# zeta2rework_lw_v28_rework.net
KiCad netlist of a schematic drawn in EAGLE
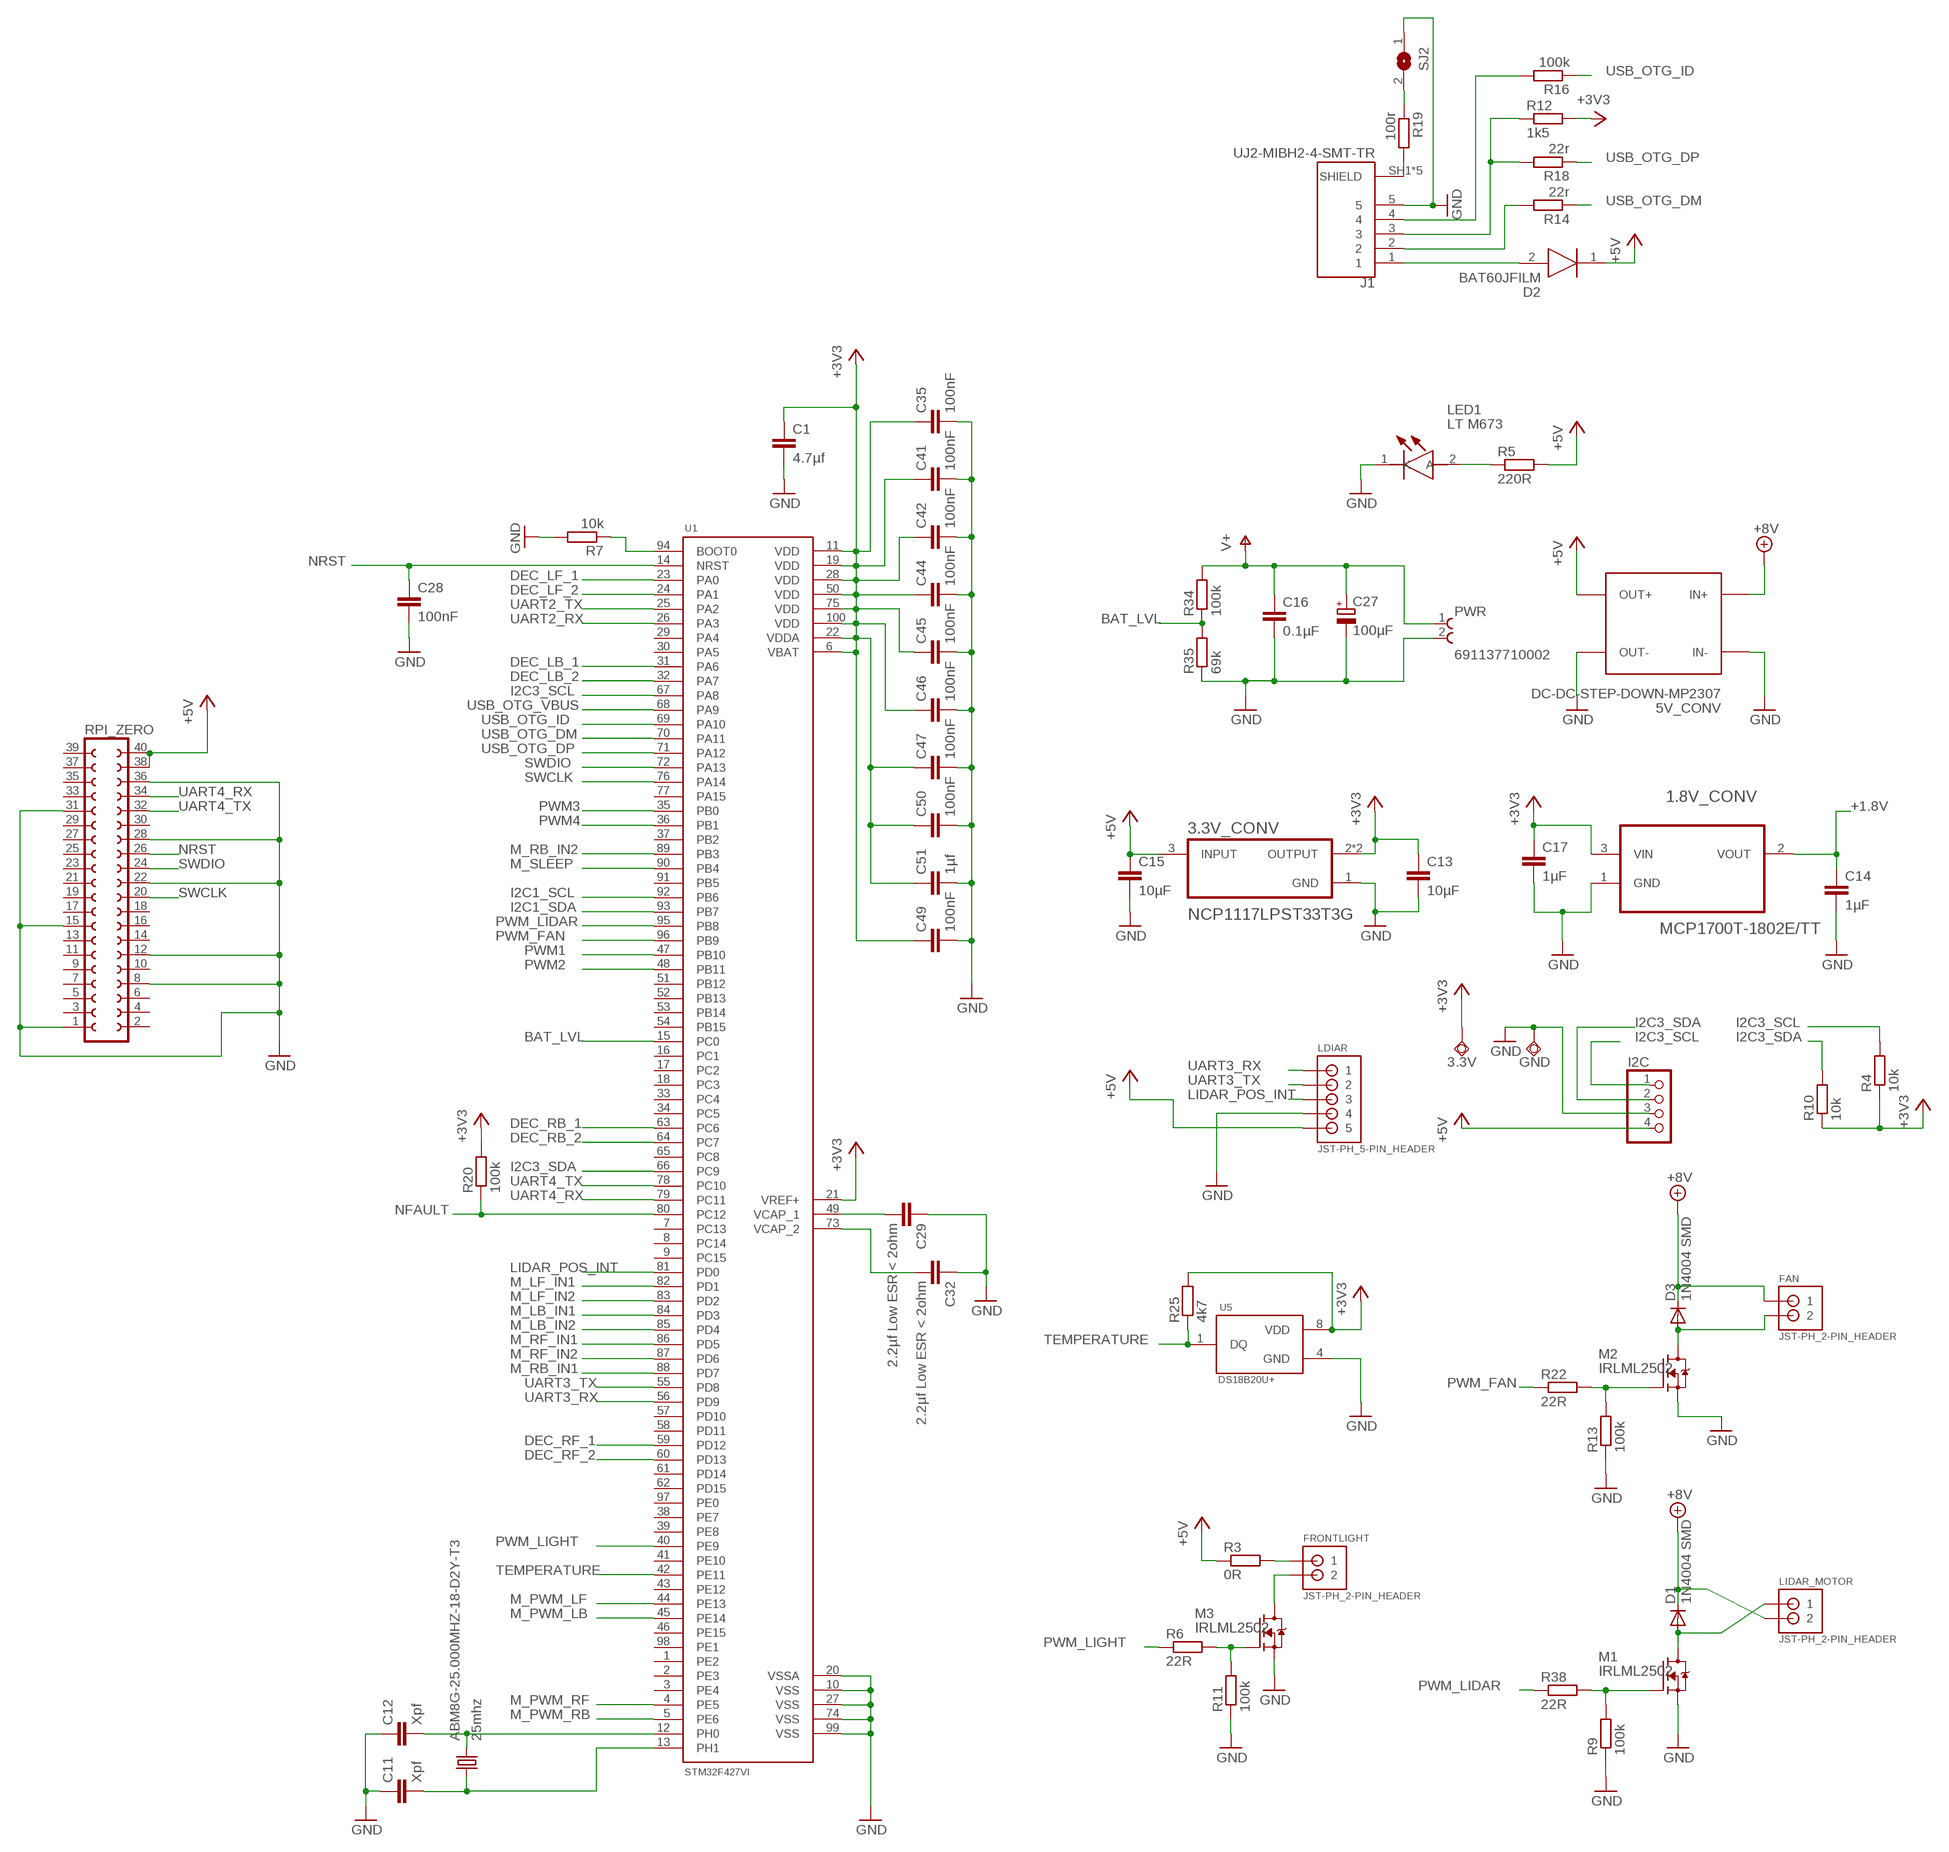
[diagram p0: schematic, sheet 1, part 1 of 2]
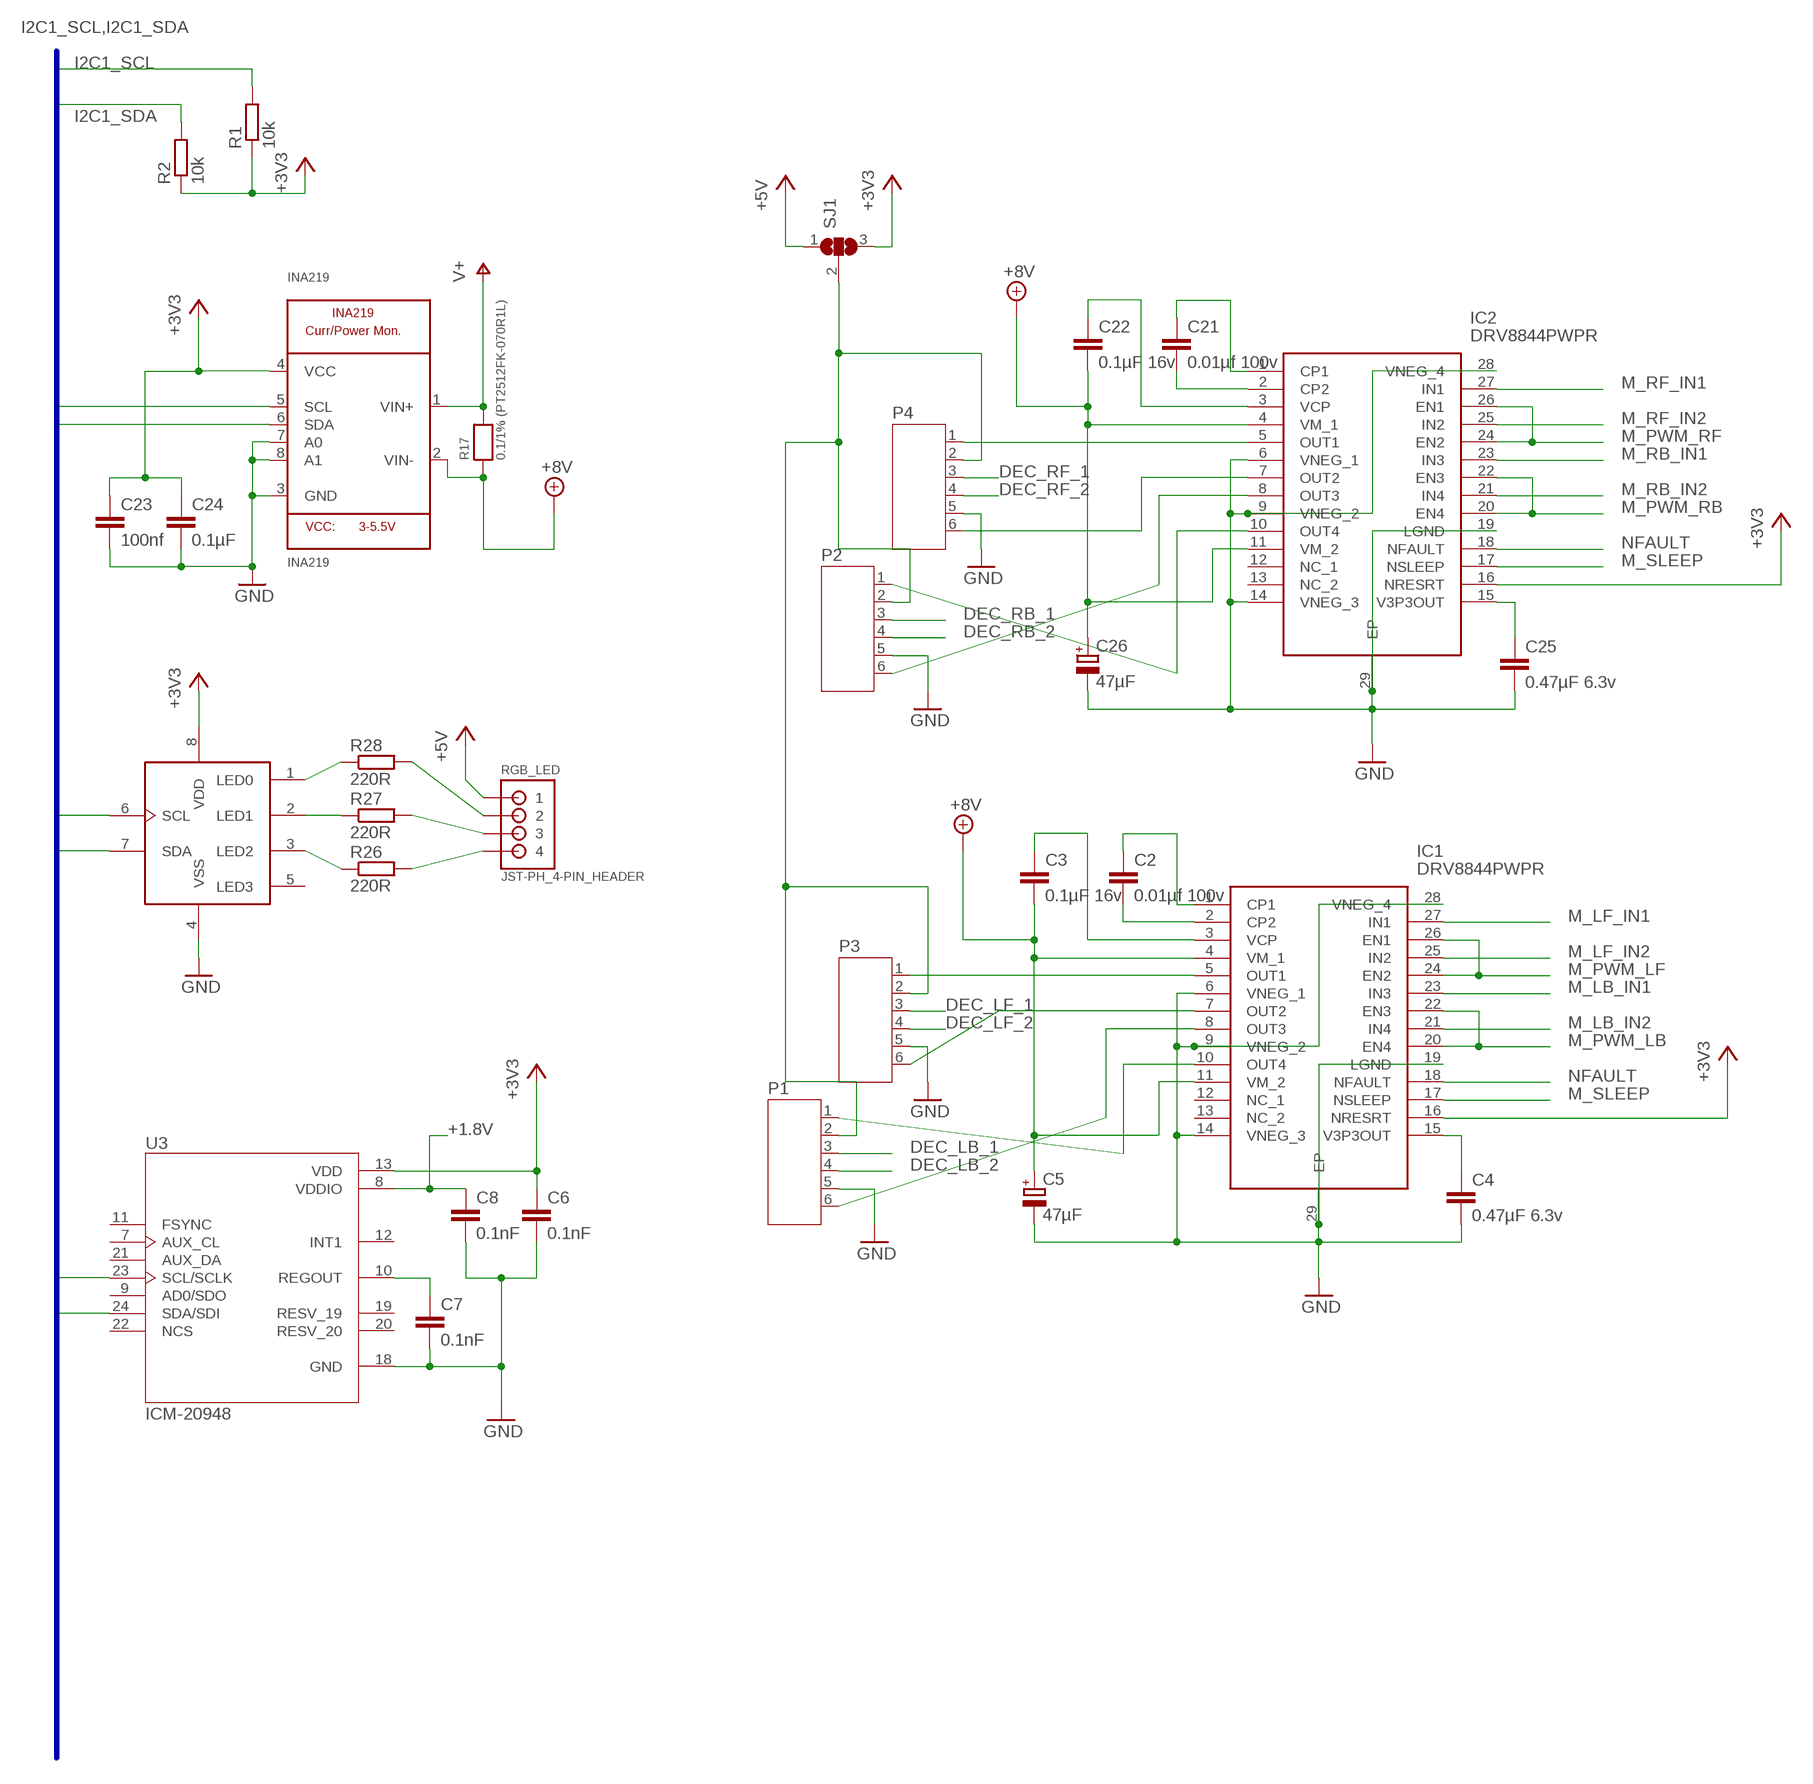
[diagram p1: schematic, sheet 1, part 2 of 2]

(export (version "E")
  (design (tool "Eeschema 10.0.6"))
  (components
    (comp (ref "1.8V_CONV")
      (value "MCP1700T-1802E/TT")
      (footprint "eagle-import:SOT95P237X112-3N")
      (fields (field (name "MF") "Microchip") (field (name "MP") "MCP1700T-2102E/TT"))
      (libsource (lib "eagle-import") (part "MCP1700T-2102E/TT"))
    )
    (comp (ref "3.3V")
      (value "TPSQTP20R")
      (footprint "eagle-import:TP20R")
      (libsource (lib "eagle-import") (part "TPSQTP20R"))
    )
    (comp (ref "3.3V_CONV")
      (value "NCP1117LPST33T3G")
      (footprint "eagle-import:SOT230P700X175-4N")
      (fields (field (name "MF") "ON Semiconductor"))
      (libsource (lib "eagle-import") (part "NCP1117LPST33T3G"))
    )
    (comp (ref "5V_CONV")
      (value "DC-DC-STEP-DOWN-MP2307")
      (footprint "eagle-import:DC-DC-STEP-DOWN-MP2307")
      (libsource (lib "eagle-import") (part "DC-DC-STEP-DOWN-MP2307"))
    )
    (comp (ref "ABM8G-25.000MHZ-18-D2Y-T3")
      (value "25mhz")
      (footprint "eagle-import:5.0X3.2_KX-9A")
      (libsource (lib "eagle-import") (part "KX-9A"))
    )
    (comp (ref "C1")
      (value "4.7µf")
      (footprint "eagle-import:C0603")
      (libsource (lib "eagle-import") (part "C-EUC0603"))
    )
    (comp (ref "C2")
      (value "0.01µf 100v")
      (footprint "eagle-import:C0603")
      (libsource (lib "eagle-import") (part "C-EUC0603"))
    )
    (comp (ref "C3")
      (value "0.1µF 16v")
      (footprint "eagle-import:C0603")
      (libsource (lib "eagle-import") (part "C-EUC0603"))
    )
    (comp (ref "C4")
      (value "0.47µF 6.3v")
      (footprint "eagle-import:C0603")
      (libsource (lib "eagle-import") (part "C-EUC0603"))
    )
    (comp (ref "C5")
      (value "47µF")
      (footprint "eagle-import:UD-5X5,8_NICHICON")
      (libsource (lib "eagle-import") (part "CPOL-EUUD-5X5,8"))
    )
    (comp (ref "C6")
      (value "0.1nF")
      (footprint "eagle-import:C0603")
      (libsource (lib "eagle-import") (part "C-EUC0603"))
    )
    (comp (ref "C7")
      (value "0.1nF")
      (footprint "eagle-import:C0603")
      (libsource (lib "eagle-import") (part "C-EUC0603"))
    )
    (comp (ref "C8")
      (value "0.1nF")
      (footprint "eagle-import:C0603")
      (libsource (lib "eagle-import") (part "C-EUC0603"))
    )
    (comp (ref "C11")
      (value "Xpf")
      (footprint "eagle-import:C0603")
      (libsource (lib "eagle-import") (part "C-EUC0603"))
    )
    (comp (ref "C12")
      (value "Xpf")
      (footprint "eagle-import:C0603")
      (libsource (lib "eagle-import") (part "C-EUC0603"))
    )
    (comp (ref "C13")
      (value "10µF")
      (footprint "eagle-import:C1206")
      (libsource (lib "eagle-import") (part "C-EUC1206"))
    )
    (comp (ref "C14")
      (value "1µF")
      (footprint "eagle-import:C0603")
      (libsource (lib "eagle-import") (part "C-EUC0603"))
    )
    (comp (ref "C15")
      (value "10µF")
      (footprint "eagle-import:C1206")
      (libsource (lib "eagle-import") (part "C-EUC1206"))
    )
    (comp (ref "C16")
      (value "0.1µF")
      (footprint "eagle-import:C0603")
      (libsource (lib "eagle-import") (part "C-EUC0603"))
    )
    (comp (ref "C17")
      (value "1µF")
      (footprint "eagle-import:C0603")
      (libsource (lib "eagle-import") (part "C-EUC0603"))
    )
    (comp (ref "C21")
      (value "0.01µf 100v")
      (footprint "eagle-import:C0603")
      (libsource (lib "eagle-import") (part "C-EUC0603"))
    )
    (comp (ref "C22")
      (value "0.1µF 16v")
      (footprint "eagle-import:C0603")
      (libsource (lib "eagle-import") (part "C-EUC0603"))
    )
    (comp (ref "C23")
      (value "100nf")
      (footprint "eagle-import:C0603")
      (libsource (lib "eagle-import") (part "C-EUC0603"))
    )
    (comp (ref "C24")
      (value "0.1µF")
      (footprint "eagle-import:C0603")
      (libsource (lib "eagle-import") (part "C-EUC0603"))
    )
    (comp (ref "C25")
      (value "0.47µF 6.3v")
      (footprint "eagle-import:C0603")
      (libsource (lib "eagle-import") (part "C-EUC0603"))
    )
    (comp (ref "C26")
      (value "47µF")
      (footprint "eagle-import:UD-5X5,8_NICHICON")
      (libsource (lib "eagle-import") (part "CPOL-EUUD-5X5,8"))
    )
    (comp (ref "C27")
      (value "100µF")
      (footprint "eagle-import:UD-5X5,8_NICHICON")
      (libsource (lib "eagle-import") (part "CPOL-EUUD-5X5,8"))
    )
    (comp (ref "C28")
      (value "100nF")
      (footprint "eagle-import:C0603")
      (libsource (lib "eagle-import") (part "C-EUC0603"))
    )
    (comp (ref "C29")
      (value "2.2µf Low ESR < 2ohm")
      (footprint "eagle-import:C1206")
      (libsource (lib "eagle-import") (part "C-EUC1206"))
    )
    (comp (ref "C32")
      (value "2.2µf Low ESR < 2ohm")
      (footprint "eagle-import:C1206")
      (libsource (lib "eagle-import") (part "C-EUC1206"))
    )
    (comp (ref "C35")
      (value "100nF")
      (footprint "eagle-import:C0603")
      (libsource (lib "eagle-import") (part "C-EUC0603"))
    )
    (comp (ref "C41")
      (value "100nF")
      (footprint "eagle-import:C0603")
      (libsource (lib "eagle-import") (part "C-EUC0603"))
    )
    (comp (ref "C42")
      (value "100nF")
      (footprint "eagle-import:C0603")
      (libsource (lib "eagle-import") (part "C-EUC0603"))
    )
    (comp (ref "C44")
      (value "100nF")
      (footprint "eagle-import:C0603")
      (libsource (lib "eagle-import") (part "C-EUC0603"))
    )
    (comp (ref "C45")
      (value "100nF")
      (footprint "eagle-import:C0603")
      (libsource (lib "eagle-import") (part "C-EUC0603"))
    )
    (comp (ref "C46")
      (value "100nF")
      (footprint "eagle-import:C0603")
      (libsource (lib "eagle-import") (part "C-EUC0603"))
    )
    (comp (ref "C47")
      (value "100nF")
      (footprint "eagle-import:C0603")
      (libsource (lib "eagle-import") (part "C-EUC0603"))
    )
    (comp (ref "C49")
      (value "100nF")
      (footprint "eagle-import:C0603")
      (libsource (lib "eagle-import") (part "C-EUC0603"))
    )
    (comp (ref "C50")
      (value "100nF")
      (footprint "eagle-import:C0603")
      (libsource (lib "eagle-import") (part "C-EUC0603"))
    )
    (comp (ref "C51")
      (value "1µf")
      (footprint "eagle-import:C0603")
      (libsource (lib "eagle-import") (part "C-EUC0603"))
    )
    (comp (ref "D1")
      (value "1N4004 SMD")
      (footprint "eagle-import:DO214AC")
      (libsource (lib "eagle-import") (part "DIODE-DO214AC"))
    )
    (comp (ref "D2")
      (value "BAT60JFILM")
      (footprint "eagle-import:SOD2513X117N")
      (fields (field (name "MOUSER_PART_NUMBER") "511-BAT60JFILM") (field (name "RS_PART_NUMBER") "1458781"))
      (libsource (lib "eagle-import") (part "BAT60JFILM"))
    )
    (comp (ref "D3")
      (value "1N4004 SMD")
      (footprint "eagle-import:DO214AC")
      (libsource (lib "eagle-import") (part "DIODE-DO214AC"))
    )
    (comp (ref "FAN")
      (value "JST-PH_2-PIN_HEADER")
      (footprint "eagle-import:JST_B2B-PH_HEADER")
      (libsource (lib "eagle-import") (part "JST-PH_2-PIN_HEADER"))
    )
    (comp (ref "FRONTLIGHT")
      (value "JST-PH_2-PIN_HEADER")
      (footprint "eagle-import:JST_B2B-PH_HEADER")
      (libsource (lib "eagle-import") (part "JST-PH_2-PIN_HEADER"))
    )
    (comp (ref "GND")
      (value "TPSQTP20R")
      (footprint "eagle-import:TP20R")
      (libsource (lib "eagle-import") (part "TPSQTP20R"))
    )
    (comp (ref "I2C")
      (value "PINHD-1X4")
      (footprint "eagle-import:1X04")
      (libsource (lib "eagle-import") (part "PINHD-1X4"))
    )
    (comp (ref "IC1")
      (value "DRV8844PWPR")
      (footprint "eagle-import:SOP65P640X120-29N")
      (fields (field (name "MOUSER_PART_NUMBER") "595-DRV8844PWPR"))
      (libsource (lib "eagle-import") (part "DRV8844PWPR"))
    )
    (comp (ref "IC2")
      (value "DRV8844PWPR")
      (footprint "eagle-import:SOP65P640X120-29N")
      (fields (field (name "MOUSER_PART_NUMBER") "595-DRV8844PWPR"))
      (libsource (lib "eagle-import") (part "DRV8844PWPR"))
    )
    (comp (ref "INA219")
      (value "INA219")
      (footprint "eagle-import:SOT23-8")
      (fields (field (name "MF") "Texas Instruments"))
      (libsource (lib "eagle-import") (part "INA219"))
    )
    (comp (ref "J1")
      (value "UJ2-MIBH2-4-SMT-TR")
      (footprint "eagle-import:CUI_UJ2-MIBH2-4-SMT-TR")
      (fields (field (name "MF") "CUI Inc."))
      (libsource (lib "eagle-import") (part "UJ2-MIBH2-4-SMT-TR"))
    )
    (comp (ref "LDIAR")
      (value "JST-PH_5-PIN_HEADER")
      (footprint "eagle-import:JST_B5B-PH_HEADER")
      (libsource (lib "eagle-import") (part "JST-PH_5-PIN_HEADER"))
    )
    (comp (ref "LED1")
      (value "LT M673")
      (footprint "eagle-import:LTM673-N1R2-25")
      (fields
        (field (name "MANUFACTURER_PART_NUMBER") "LT M673-N1R2-25")
        (field (name "MOUSER_PART_NUMBER") "720-LTM673N1R225Z")
        (field (name "RS_PART_NUMBER") "9133231")
      )
      (libsource (lib "eagle-import") (part "LT_M673-N1R2-25"))
    )
    (comp (ref "LIDAR_MOTOR")
      (value "JST-PH_2-PIN_HEADER")
      (footprint "eagle-import:JST_B2B-PH_HEADER")
      (libsource (lib "eagle-import") (part "JST-PH_2-PIN_HEADER"))
    )
    (comp (ref "M1")
      (value "IRLML2502")
      (footprint "eagle-import:SOT23")
      (fields (field (name "MF") "Infineon") (field (name "MP") "IRLML2502TRPBF"))
      (libsource (lib "eagle-import") (part "IRLML2502TRPBF"))
    )
    (comp (ref "M2")
      (value "IRLML2502")
      (footprint "eagle-import:SOT23")
      (fields (field (name "MF") "Infineon") (field (name "MP") "IRLML2502TRPBF"))
      (libsource (lib "eagle-import") (part "IRLML2502TRPBF"))
    )
    (comp (ref "M3")
      (value "IRLML2502")
      (footprint "eagle-import:SOT23")
      (fields (field (name "MF") "Infineon") (field (name "MP") "IRLML2502TRPBF"))
      (libsource (lib "eagle-import") (part "IRLML2502TRPBF"))
    )
    (comp (ref "P1")
      (value "JST-PH6")
      (footprint "eagle-import:JST-PH6")
      (libsource (lib "eagle-import") (part "JST-PH6"))
    )
    (comp (ref "P2")
      (value "JST-PH6")
      (footprint "eagle-import:JST-PH6")
      (libsource (lib "eagle-import") (part "JST-PH6"))
    )
    (comp (ref "P3")
      (value "JST-PH6")
      (footprint "eagle-import:JST-PH6")
      (libsource (lib "eagle-import") (part "JST-PH6"))
    )
    (comp (ref "P4")
      (value "JST-PH6")
      (footprint "eagle-import:JST-PH6")
      (libsource (lib "eagle-import") (part "JST-PH6"))
    )
    (comp (ref "PCA9533")
      (value "PCA9533")
      (footprint "eagle-import:SOIC8")
      (libsource (lib "eagle-import") (part "PCA9533"))
    )
    (comp (ref "PWR")
      (value "691137710002")
      (footprint "eagle-import:691137710002")
      (fields (field (name "MF") "Wurth Electronics"))
      (libsource (lib "eagle-import") (part "691137710002"))
    )
    (comp (ref "R1")
      (value "10k")
      (footprint "eagle-import:R0603")
      (libsource (lib "eagle-import") (part "R-EU_R0603"))
    )
    (comp (ref "R2")
      (value "10k")
      (footprint "eagle-import:R0603")
      (libsource (lib "eagle-import") (part "R-EU_R0603"))
    )
    (comp (ref "R3")
      (value "0R")
      (footprint "eagle-import:R0603")
      (libsource (lib "eagle-import") (part "R-EU_R0603"))
    )
    (comp (ref "R4")
      (value "10k")
      (footprint "eagle-import:R0603")
      (libsource (lib "eagle-import") (part "R-EU_R0603"))
    )
    (comp (ref "R5")
      (value "220R")
      (footprint "eagle-import:R0603")
      (libsource (lib "eagle-import") (part "R-EU_R0603"))
    )
    (comp (ref "R6")
      (value "22R")
      (footprint "eagle-import:R0603")
      (libsource (lib "eagle-import") (part "R-EU_R0603"))
    )
    (comp (ref "R7")
      (value "10k")
      (footprint "eagle-import:R0603")
      (libsource (lib "eagle-import") (part "R-EU_R0603"))
    )
    (comp (ref "R9")
      (value "100k")
      (footprint "eagle-import:R0603")
      (libsource (lib "eagle-import") (part "R-EU_R0603"))
    )
    (comp (ref "R10")
      (value "10k")
      (footprint "eagle-import:R0603")
      (libsource (lib "eagle-import") (part "R-EU_R0603"))
    )
    (comp (ref "R11")
      (value "100k")
      (footprint "eagle-import:R0603")
      (libsource (lib "eagle-import") (part "R-EU_R0603"))
    )
    (comp (ref "R12")
      (value "1k5")
      (footprint "eagle-import:R0603")
      (libsource (lib "eagle-import") (part "R-EU_R0603"))
    )
    (comp (ref "R13")
      (value "100k")
      (footprint "eagle-import:R0603")
      (libsource (lib "eagle-import") (part "R-EU_R0603"))
    )
    (comp (ref "R14")
      (value "22r")
      (footprint "eagle-import:R0603")
      (libsource (lib "eagle-import") (part "R-EU_R0603"))
    )
    (comp (ref "R16")
      (value "100k")
      (footprint "eagle-import:R0603")
      (libsource (lib "eagle-import") (part "R-EU_R0603"))
    )
    (comp (ref "R17")
      (value "0.1/1% (PT2512FK-070R1L)")
      (footprint "eagle-import:2512")
      (libsource (lib "eagle-import") (part "RESISTOR2512"))
    )
    (comp (ref "R18")
      (value "22r")
      (footprint "eagle-import:R0603")
      (libsource (lib "eagle-import") (part "R-EU_R0603"))
    )
    (comp (ref "R19")
      (value "100r")
      (footprint "eagle-import:R0603")
      (libsource (lib "eagle-import") (part "R-EU_R0603"))
    )
    (comp (ref "R20")
      (value "100k")
      (footprint "eagle-import:R0603")
      (libsource (lib "eagle-import") (part "R-EU_R0603"))
    )
    (comp (ref "R22")
      (value "22R")
      (footprint "eagle-import:R0603")
      (libsource (lib "eagle-import") (part "R-EU_R0603"))
    )
    (comp (ref "R25")
      (value "4k7")
      (footprint "eagle-import:R0603")
      (libsource (lib "eagle-import") (part "R-EU_R0603"))
    )
    (comp (ref "R26")
      (value "220R")
      (footprint "eagle-import:R0603")
      (libsource (lib "eagle-import") (part "R-EU_R0603"))
    )
    (comp (ref "R27")
      (value "220R")
      (footprint "eagle-import:R0603")
      (libsource (lib "eagle-import") (part "R-EU_R0603"))
    )
    (comp (ref "R28")
      (value "220R")
      (footprint "eagle-import:R0603")
      (libsource (lib "eagle-import") (part "R-EU_R0603"))
    )
    (comp (ref "R34")
      (value "100k")
      (footprint "eagle-import:R0603")
      (libsource (lib "eagle-import") (part "R-EU_R0603"))
    )
    (comp (ref "R35")
      (value "69k")
      (footprint "eagle-import:R0603")
      (libsource (lib "eagle-import") (part "R-EU_R0603"))
    )
    (comp (ref "R38")
      (value "22R")
      (footprint "eagle-import:R0603")
      (libsource (lib "eagle-import") (part "R-EU_R0603"))
    )
    (comp (ref "RGB_LED")
      (value "JST-PH_4-PIN_HEADER")
      (footprint "eagle-import:JST_B4B-PH_HEADER")
      (libsource (lib "eagle-import") (part "JST-PH_4-PIN_HEADER"))
    )
    (comp (ref "RPI_ZERO")
      (value "FE20-2")
      (footprint "eagle-import:FE20-2")
      (libsource (lib "eagle-import") (part "FE20-2"))
    )
    (comp (ref "SJ1")
      (value "SJ2W")
      (footprint "eagle-import:SJ_2")
      (libsource (lib "eagle-import") (part "SJ2W"))
    )
    (comp (ref "SJ2") (value "SJ") (footprint "eagle-import:SJ") (libsource (lib "eagle-import") (part "SJ")))
    (comp (ref "U1")
      (value "STM32F427VI")
      (footprint "eagle-import:QFP50P1600X1600X160-100N")
      (fields (field (name "MF") "STMicroelectronics") (field (name "MP") "STM32F427VGT7"))
      (libsource (lib "eagle-import") (part "STM32F427VGT7"))
    )
    (comp (ref "U3")
      (value "ICM-20948")
      (footprint "eagle-import:QFN40P300X300X105-25N")
      (fields (field (name "MF") "TDK InvenSense"))
      (libsource (lib "eagle-import") (part "ICM-20948"))
    )
    (comp (ref "U5")
      (value "DS18B20U+")
      (footprint "eagle-import:SOP65P490X95-8N")
      (fields (field (name "MF") "Maxim"))
      (libsource (lib "eagle-import") (part "DS18B20U+"))
    )
  )
  (nets
    (net (code "1") (name "+3V3") (class "Default")
      (node (ref "1.8V_CONV") (pin "3") (pinfunction "VIN_3") (pintype "input"))
      (node (ref "3.3V") (pin "TP") (pinfunction "TP_TP") (pintype "input"))
      (node (ref "3.3V_CONV") (pin "2") (pinfunction "OUTPUT_2") (pintype "output"))
      (node (ref "3.3V_CONV") (pin "4") (pinfunction "OUTPUT_4") (pintype "output"))
      (node (ref "C1") (pin "1") (pinfunction "1_1") (pintype "passive"))
      (node (ref "C13") (pin "1") (pinfunction "1_1") (pintype "passive"))
      (node (ref "C17") (pin "1") (pinfunction "1_1") (pintype "passive"))
      (node (ref "C23") (pin "1") (pinfunction "1_1") (pintype "passive"))
      (node (ref "C24") (pin "1") (pinfunction "1_1") (pintype "passive"))
      (node (ref "C35") (pin "1") (pinfunction "1_1") (pintype "passive"))
      (node (ref "C41") (pin "1") (pinfunction "1_1") (pintype "passive"))
      (node (ref "C42") (pin "1") (pinfunction "1_1") (pintype "passive"))
      (node (ref "C44") (pin "1") (pinfunction "1_1") (pintype "passive"))
      (node (ref "C45") (pin "1") (pinfunction "1_1") (pintype "passive"))
      (node (ref "C46") (pin "1") (pinfunction "1_1") (pintype "passive"))
      (node (ref "C47") (pin "1") (pinfunction "1_1") (pintype "passive"))
      (node (ref "C49") (pin "1") (pinfunction "1_1") (pintype "passive"))
      (node (ref "C50") (pin "1") (pinfunction "1_1") (pintype "passive"))
      (node (ref "C51") (pin "1") (pinfunction "1_1") (pintype "passive"))
      (node (ref "C6") (pin "1") (pinfunction "1_1") (pintype "passive"))
      (node (ref "IC1") (pin "16") (pinfunction "NRESRT_16") (pintype "bidirectional"))
      (node (ref "IC2") (pin "16") (pinfunction "NRESRT_16") (pintype "bidirectional"))
      (node (ref "INA219") (pin "4") (pinfunction "VCC_4") (pintype "bidirectional"))
      (node (ref "PCA9533") (pin "8") (pinfunction "VDD_8") (pintype "power_in"))
      (node (ref "R1") (pin "1") (pinfunction "1_1") (pintype "passive"))
      (node (ref "R10") (pin "1") (pinfunction "1_1") (pintype "passive"))
      (node (ref "R12") (pin "2") (pinfunction "2_2") (pintype "passive"))
      (node (ref "R2") (pin "1") (pinfunction "1_1") (pintype "passive"))
      (node (ref "R20") (pin "2") (pinfunction "2_2") (pintype "passive"))
      (node (ref "R25") (pin "2") (pinfunction "2_2") (pintype "passive"))
      (node (ref "R4") (pin "1") (pinfunction "1_1") (pintype "passive"))
      (node (ref "SJ1") (pin "3") (pinfunction "3_3") (pintype "passive"))
      (node (ref "U1") (pin "100") (pinfunction "VDD_100") (pintype "power_in"))
      (node (ref "U1") (pin "11") (pinfunction "VDD_11") (pintype "power_in"))
      (node (ref "U1") (pin "19") (pinfunction "VDD_19") (pintype "power_in"))
      (node (ref "U1") (pin "21") (pinfunction "VREF+_21") (pintype "power_in"))
      (node (ref "U1") (pin "22") (pinfunction "VDDA_22") (pintype "power_in"))
      (node (ref "U1") (pin "28") (pinfunction "VDD_28") (pintype "power_in"))
      (node (ref "U1") (pin "50") (pinfunction "VDD_50") (pintype "power_in"))
      (node (ref "U1") (pin "6") (pinfunction "VBAT_6") (pintype "power_in"))
      (node (ref "U1") (pin "75") (pinfunction "VDD_75") (pintype "power_in"))
      (node (ref "U3") (pin "13") (pinfunction "VDD_13") (pintype "power_in"))
      (node (ref "U5") (pin "8") (pinfunction "VDD_8") (pintype "power_in"))
    )
    (net (code "2") (name "+5V") (class "Default")
      (node (ref "3.3V_CONV") (pin "3") (pinfunction "INPUT_3") (pintype "input"))
      (node (ref "5V_CONV") (pin "OUT+") (pinfunction "OUT+_OUT+") (pintype "bidirectional"))
      (node (ref "C15") (pin "1") (pinfunction "1_1") (pintype "passive"))
      (node (ref "D2") (pin "1") (pinfunction "K_1") (pintype "bidirectional"))
      (node (ref "I2C") (pin "4") (pinfunction "4_4") (pintype "passive"))
      (node (ref "LDIAR") (pin "P5") (pinfunction "5_P5") (pintype "bidirectional"))
      (node (ref "R3") (pin "1") (pinfunction "1_1") (pintype "passive"))
      (node (ref "R5") (pin "2") (pinfunction "2_2") (pintype "passive"))
      (node (ref "RGB_LED") (pin "P1") (pinfunction "1_P1") (pintype "bidirectional"))
      (node (ref "RPI_ZERO") (pin "38") (pinfunction "38_38") (pintype "passive"))
      (node (ref "RPI_ZERO") (pin "40") (pinfunction "40_40") (pintype "passive"))
      (node (ref "SJ1") (pin "1") (pinfunction "1_1") (pintype "passive"))
    )
    (net (code "3") (name "+8V") (class "Default")
      (node (ref "5V_CONV") (pin "IN+") (pinfunction "IN+_IN+") (pintype "bidirectional"))
      (node (ref "C22") (pin "2") (pinfunction "2_2") (pintype "passive"))
      (node (ref "C26") (pin "+") (pinfunction "+_+") (pintype "passive"))
      (node (ref "C3") (pin "2") (pinfunction "2_2") (pintype "passive"))
      (node (ref "C5") (pin "+") (pinfunction "+_+") (pintype "passive"))
      (node (ref "D1") (pin "C") (pinfunction "C_C") (pintype "passive"))
      (node (ref "D3") (pin "C") (pinfunction "C_C") (pintype "passive"))
      (node (ref "FAN") (pin "P1") (pinfunction "1_P1") (pintype "bidirectional"))
      (node (ref "IC1") (pin "11") (pinfunction "VM_2_11") (pintype "bidirectional"))
      (node (ref "IC1") (pin "4") (pinfunction "VM_1_4") (pintype "bidirectional"))
      (node (ref "IC2") (pin "11") (pinfunction "VM_2_11") (pintype "bidirectional"))
      (node (ref "IC2") (pin "4") (pinfunction "VM_1_4") (pintype "bidirectional"))
      (node (ref "INA219") (pin "2") (pinfunction "VIN-_2") (pintype "bidirectional"))
      (node (ref "LIDAR_MOTOR") (pin "P2") (pinfunction "2_P2") (pintype "bidirectional"))
      (node (ref "R17") (pin "1") (pinfunction "1_1") (pintype "passive"))
    )
    (net (code "4") (name "/+1.8V") (class "Default")
      (node (ref "1.8V_CONV") (pin "2") (pinfunction "VOUT_2") (pintype "output"))
      (node (ref "C14") (pin "1") (pinfunction "1_1") (pintype "passive"))
      (node (ref "C8") (pin "1") (pinfunction "1_1") (pintype "passive"))
      (node (ref "U3") (pin "8") (pinfunction "VDDIO_8") (pintype "power_in"))
    )
    (net (code "5") (name "/BAT_LVL") (class "Default")
      (node (ref "R34") (pin "1") (pinfunction "1_1") (pintype "passive"))
      (node (ref "R35") (pin "2") (pinfunction "2_2") (pintype "passive"))
      (node (ref "U1") (pin "15") (pinfunction "PC0_15") (pintype "bidirectional"))
    )
    (net (code "6") (name "/DEC_LB_1") (class "Default")
      (node (ref "P1") (pin "3") (pinfunction "3_3") (pintype "passive"))
      (node (ref "U1") (pin "31") (pinfunction "PA6_31") (pintype "bidirectional"))
    )
    (net (code "7") (name "/DEC_LB_2") (class "Default")
      (node (ref "P1") (pin "4") (pinfunction "4_4") (pintype "passive"))
      (node (ref "U1") (pin "32") (pinfunction "PA7_32") (pintype "bidirectional"))
    )
    (net (code "8") (name "/DEC_LF_1") (class "Default")
      (node (ref "P3") (pin "3") (pinfunction "3_3") (pintype "passive"))
      (node (ref "U1") (pin "23") (pinfunction "PA0_23") (pintype "bidirectional"))
    )
    (net (code "9") (name "/DEC_LF_2") (class "Default")
      (node (ref "P3") (pin "4") (pinfunction "4_4") (pintype "passive"))
      (node (ref "U1") (pin "24") (pinfunction "PA1_24") (pintype "bidirectional"))
    )
    (net (code "10") (name "/DEC_RB_1") (class "Default")
      (node (ref "P2") (pin "3") (pinfunction "3_3") (pintype "passive"))
      (node (ref "U1") (pin "63") (pinfunction "PC6_63") (pintype "bidirectional"))
    )
    (net (code "11") (name "/DEC_RB_2") (class "Default")
      (node (ref "P2") (pin "4") (pinfunction "4_4") (pintype "passive"))
      (node (ref "U1") (pin "64") (pinfunction "PC7_64") (pintype "bidirectional"))
    )
    (net (code "12") (name "/DEC_RF_1") (class "Default")
      (node (ref "P4") (pin "3") (pinfunction "3_3") (pintype "passive"))
      (node (ref "U1") (pin "59") (pinfunction "PD12_59") (pintype "bidirectional"))
    )
    (net (code "13") (name "/DEC_RF_2") (class "Default")
      (node (ref "P4") (pin "4") (pinfunction "4_4") (pintype "passive"))
      (node (ref "U1") (pin "60") (pinfunction "PD13_60") (pintype "bidirectional"))
    )
    (net (code "14") (name "/I2C1_SCL") (class "Default")
      (node (ref "INA219") (pin "5") (pinfunction "SCL_5") (pintype "bidirectional"))
      (node (ref "PCA9533") (pin "6") (pinfunction "SCL_6") (pintype "input"))
      (node (ref "R1") (pin "2") (pinfunction "2_2") (pintype "passive"))
      (node (ref "U1") (pin "92") (pinfunction "PB6_92") (pintype "bidirectional"))
      (node (ref "U3") (pin "23") (pinfunction "SCL/SCLK_23") (pintype "input"))
    )
    (net (code "15") (name "/I2C1_SDA") (class "Default")
      (node (ref "INA219") (pin "6") (pinfunction "SDA_6") (pintype "bidirectional"))
      (node (ref "PCA9533") (pin "7") (pinfunction "SDA_7") (pintype "bidirectional"))
      (node (ref "R2") (pin "2") (pinfunction "2_2") (pintype "passive"))
      (node (ref "U1") (pin "93") (pinfunction "PB7_93") (pintype "bidirectional"))
      (node (ref "U3") (pin "24") (pinfunction "SDA/SDI_24") (pintype "bidirectional"))
    )
    (net (code "16") (name "/I2C3_SCL") (class "Default")
      (node (ref "I2C") (pin "1") (pinfunction "1_1") (pintype "passive"))
      (node (ref "R4") (pin "2") (pinfunction "2_2") (pintype "passive"))
      (node (ref "U1") (pin "67") (pinfunction "PA8_67") (pintype "bidirectional"))
    )
    (net (code "17") (name "/I2C3_SDA") (class "Default")
      (node (ref "I2C") (pin "2") (pinfunction "2_2") (pintype "passive"))
      (node (ref "R10") (pin "2") (pinfunction "2_2") (pintype "passive"))
      (node (ref "U1") (pin "66") (pinfunction "PC9_66") (pintype "bidirectional"))
    )
    (net (code "18") (name "/LIDAR_POS_INT") (class "Default")
      (node (ref "LDIAR") (pin "P3") (pinfunction "3_P3") (pintype "bidirectional"))
      (node (ref "U1") (pin "81") (pinfunction "PD0_81") (pintype "bidirectional"))
    )
    (net (code "19") (name "/M_LB_IN1") (class "Default")
      (node (ref "IC1") (pin "23") (pinfunction "IN3_23") (pintype "input"))
      (node (ref "U1") (pin "84") (pinfunction "PD3_84") (pintype "bidirectional"))
    )
    (net (code "20") (name "/M_LB_IN2") (class "Default")
      (node (ref "IC1") (pin "21") (pinfunction "IN4_21") (pintype "input"))
      (node (ref "U1") (pin "85") (pinfunction "PD4_85") (pintype "bidirectional"))
    )
    (net (code "21") (name "/M_LF_IN1") (class "Default")
      (node (ref "IC1") (pin "27") (pinfunction "IN1_27") (pintype "input"))
      (node (ref "U1") (pin "82") (pinfunction "PD1_82") (pintype "bidirectional"))
    )
    (net (code "22") (name "/M_LF_IN2") (class "Default")
      (node (ref "IC1") (pin "25") (pinfunction "IN2_25") (pintype "input"))
      (node (ref "U1") (pin "83") (pinfunction "PD2_83") (pintype "bidirectional"))
    )
    (net (code "23") (name "/M_PWM_LB") (class "Default")
      (node (ref "IC1") (pin "20") (pinfunction "EN4_20") (pintype "bidirectional"))
      (node (ref "IC1") (pin "22") (pinfunction "EN3_22") (pintype "bidirectional"))
      (node (ref "U1") (pin "45") (pinfunction "PE14_45") (pintype "bidirectional"))
    )
    (net (code "24") (name "/M_PWM_LF") (class "Default")
      (node (ref "IC1") (pin "24") (pinfunction "EN2_24") (pintype "bidirectional"))
      (node (ref "IC1") (pin "26") (pinfunction "EN1_26") (pintype "bidirectional"))
      (node (ref "U1") (pin "44") (pinfunction "PE13_44") (pintype "bidirectional"))
    )
    (net (code "25") (name "/M_PWM_RB") (class "Default")
      (node (ref "IC2") (pin "20") (pinfunction "EN4_20") (pintype "bidirectional"))
      (node (ref "IC2") (pin "22") (pinfunction "EN3_22") (pintype "bidirectional"))
      (node (ref "U1") (pin "5") (pinfunction "PE6_5") (pintype "bidirectional"))
    )
    (net (code "26") (name "/M_PWM_RF") (class "Default")
      (node (ref "IC2") (pin "24") (pinfunction "EN2_24") (pintype "bidirectional"))
      (node (ref "IC2") (pin "26") (pinfunction "EN1_26") (pintype "bidirectional"))
      (node (ref "U1") (pin "4") (pinfunction "PE5_4") (pintype "bidirectional"))
    )
    (net (code "27") (name "/M_RB_IN1") (class "Default")
      (node (ref "IC2") (pin "23") (pinfunction "IN3_23") (pintype "input"))
      (node (ref "U1") (pin "88") (pinfunction "PD7_88") (pintype "bidirectional"))
    )
    (net (code "28") (name "/M_RB_IN2") (class "Default")
      (node (ref "IC2") (pin "21") (pinfunction "IN4_21") (pintype "input"))
      (node (ref "U1") (pin "89") (pinfunction "PB3_89") (pintype "bidirectional"))
    )
    (net (code "29") (name "/M_RF_IN1") (class "Default")
      (node (ref "IC2") (pin "27") (pinfunction "IN1_27") (pintype "input"))
      (node (ref "U1") (pin "86") (pinfunction "PD5_86") (pintype "bidirectional"))
    )
    (net (code "30") (name "/M_RF_IN2") (class "Default")
      (node (ref "IC2") (pin "25") (pinfunction "IN2_25") (pintype "input"))
      (node (ref "U1") (pin "87") (pinfunction "PD6_87") (pintype "bidirectional"))
    )
    (net (code "31") (name "/M_SLEEP") (class "Default")
      (node (ref "IC1") (pin "17") (pinfunction "NSLEEP_17") (pintype "bidirectional"))
      (node (ref "IC2") (pin "17") (pinfunction "NSLEEP_17") (pintype "bidirectional"))
      (node (ref "U1") (pin "90") (pinfunction "PB4_90") (pintype "bidirectional"))
    )
    (net (code "32") (name "/NFAULT") (class "Default")
      (node (ref "IC1") (pin "18") (pinfunction "NFAULT_18") (pintype "bidirectional"))
      (node (ref "IC2") (pin "18") (pinfunction "NFAULT_18") (pintype "bidirectional"))
      (node (ref "R20") (pin "1") (pinfunction "1_1") (pintype "passive"))
      (node (ref "U1") (pin "80") (pinfunction "PC12_80") (pintype "bidirectional"))
    )
    (net (code "33") (name "/NRST") (class "Default")
      (node (ref "C28") (pin "1") (pinfunction "1_1") (pintype "passive"))
      (node (ref "RPI_ZERO") (pin "26") (pinfunction "26_26") (pintype "passive"))
      (node (ref "U1") (pin "14") (pinfunction "NRST_14") (pintype "bidirectional"))
    )
    (net (code "34") (name "/PWM1") (class "Default")
      (node (ref "U1") (pin "47") (pinfunction "PB10_47") (pintype "bidirectional"))
    )
    (net (code "35") (name "/PWM2") (class "Default")
      (node (ref "U1") (pin "48") (pinfunction "PB11_48") (pintype "bidirectional"))
    )
    (net (code "36") (name "/PWM3") (class "Default")
      (node (ref "U1") (pin "35") (pinfunction "PB0_35") (pintype "bidirectional"))
    )
    (net (code "37") (name "/PWM4") (class "Default")
      (node (ref "U1") (pin "36") (pinfunction "PB1_36") (pintype "bidirectional"))
    )
    (net (code "38") (name "/PWM_FAN") (class "Default")
      (node (ref "R22") (pin "1") (pinfunction "1_1") (pintype "passive"))
      (node (ref "U1") (pin "96") (pinfunction "PB9_96") (pintype "bidirectional"))
    )
    (net (code "39") (name "/PWM_LIDAR") (class "Default")
      (node (ref "R38") (pin "1") (pinfunction "1_1") (pintype "passive"))
      (node (ref "U1") (pin "95") (pinfunction "PB8_95") (pintype "bidirectional"))
    )
    (net (code "40") (name "/PWM_LIGHT") (class "Default")
      (node (ref "R6") (pin "1") (pinfunction "1_1") (pintype "passive"))
      (node (ref "U1") (pin "40") (pinfunction "PE9_40") (pintype "bidirectional"))
    )
    (net (code "41") (name "/SWCLK") (class "Default")
      (node (ref "RPI_ZERO") (pin "20") (pinfunction "20_20") (pintype "passive"))
      (node (ref "U1") (pin "76") (pinfunction "PA14_76") (pintype "bidirectional"))
    )
    (net (code "42") (name "/SWDIO") (class "Default")
      (node (ref "RPI_ZERO") (pin "24") (pinfunction "24_24") (pintype "passive"))
      (node (ref "U1") (pin "72") (pinfunction "PA13_72") (pintype "bidirectional"))
    )
    (net (code "43") (name "/TEMPERATURE") (class "Default")
      (node (ref "R25") (pin "1") (pinfunction "1_1") (pintype "passive"))
      (node (ref "U1") (pin "42") (pinfunction "PE11_42") (pintype "bidirectional"))
      (node (ref "U5") (pin "1") (pinfunction "DQ_1") (pintype "bidirectional"))
    )
    (net (code "44") (name "/UART2_RX") (class "Default")
      (node (ref "U1") (pin "26") (pinfunction "PA3_26") (pintype "bidirectional"))
    )
    (net (code "45") (name "/UART2_TX") (class "Default")
      (node (ref "U1") (pin "25") (pinfunction "PA2_25") (pintype "bidirectional"))
    )
    (net (code "46") (name "/UART3_RX") (class "Default")
      (node (ref "LDIAR") (pin "P1") (pinfunction "1_P1") (pintype "bidirectional"))
      (node (ref "U1") (pin "56") (pinfunction "PD9_56") (pintype "bidirectional"))
    )
    (net (code "47") (name "/UART3_TX") (class "Default")
      (node (ref "LDIAR") (pin "P2") (pinfunction "2_P2") (pintype "bidirectional"))
      (node (ref "U1") (pin "55") (pinfunction "PD8_55") (pintype "bidirectional"))
    )
    (net (code "48") (name "/UART4_RX") (class "Default")
      (node (ref "RPI_ZERO") (pin "34") (pinfunction "34_34") (pintype "passive"))
      (node (ref "U1") (pin "79") (pinfunction "PC11_79") (pintype "bidirectional"))
    )
    (net (code "49") (name "/UART4_TX") (class "Default")
      (node (ref "RPI_ZERO") (pin "32") (pinfunction "32_32") (pintype "passive"))
      (node (ref "U1") (pin "78") (pinfunction "PC10_78") (pintype "bidirectional"))
    )
    (net (code "50") (name "/USB_OTG_DM") (class "Default")
      (node (ref "R14") (pin "1") (pinfunction "1_1") (pintype "passive"))
      (node (ref "U1") (pin "70") (pinfunction "PA11_70") (pintype "bidirectional"))
    )
    (net (code "51") (name "/USB_OTG_DP") (class "Default")
      (node (ref "R18") (pin "1") (pinfunction "1_1") (pintype "passive"))
      (node (ref "U1") (pin "71") (pinfunction "PA12_71") (pintype "bidirectional"))
    )
    (net (code "52") (name "/USB_OTG_ID") (class "Default")
      (node (ref "R16") (pin "1") (pinfunction "1_1") (pintype "passive"))
      (node (ref "U1") (pin "69") (pinfunction "PA10_69") (pintype "bidirectional"))
    )
    (net (code "53") (name "/USB_OTG_VBUS") (class "Default")
      (node (ref "U1") (pin "68") (pinfunction "PA9_68") (pintype "bidirectional"))
    )
    (net (code "55") (name "GND") (class "Default")
      (node (ref "1.8V_CONV") (pin "1") (pinfunction "GND_1") (pintype "passive"))
      (node (ref "3.3V_CONV") (pin "1") (pinfunction "GND_1") (pintype "power_in"))
      (node (ref "5V_CONV") (pin "IN-") (pinfunction "IN-_IN-") (pintype "bidirectional"))
      (node (ref "5V_CONV") (pin "OUT-") (pinfunction "OUT-_OUT-") (pintype "bidirectional"))
      (node (ref "C1") (pin "2") (pinfunction "2_2") (pintype "passive"))
      (node (ref "C11") (pin "1") (pinfunction "1_1") (pintype "passive"))
      (node (ref "C12") (pin "1") (pinfunction "1_1") (pintype "passive"))
      (node (ref "C13") (pin "2") (pinfunction "2_2") (pintype "passive"))
      (node (ref "C14") (pin "2") (pinfunction "2_2") (pintype "passive"))
      (node (ref "C15") (pin "2") (pinfunction "2_2") (pintype "passive"))
      (node (ref "C16") (pin "2") (pinfunction "2_2") (pintype "passive"))
      (node (ref "C17") (pin "2") (pinfunction "2_2") (pintype "passive"))
      (node (ref "C23") (pin "2") (pinfunction "2_2") (pintype "passive"))
      (node (ref "C24") (pin "2") (pinfunction "2_2") (pintype "passive"))
      (node (ref "C25") (pin "2") (pinfunction "2_2") (pintype "passive"))
      (node (ref "C26") (pin "-") (pinfunction "-_-") (pintype "passive"))
      (node (ref "C27") (pin "-") (pinfunction "-_-") (pintype "passive"))
      (node (ref "C28") (pin "2") (pinfunction "2_2") (pintype "passive"))
      (node (ref "C29") (pin "1") (pinfunction "1_1") (pintype "passive"))
      (node (ref "C32") (pin "1") (pinfunction "1_1") (pintype "passive"))
      (node (ref "C35") (pin "2") (pinfunction "2_2") (pintype "passive"))
      (node (ref "C4") (pin "2") (pinfunction "2_2") (pintype "passive"))
      (node (ref "C41") (pin "2") (pinfunction "2_2") (pintype "passive"))
      (node (ref "C42") (pin "2") (pinfunction "2_2") (pintype "passive"))
      (node (ref "C44") (pin "2") (pinfunction "2_2") (pintype "passive"))
      (node (ref "C45") (pin "2") (pinfunction "2_2") (pintype "passive"))
      (node (ref "C46") (pin "2") (pinfunction "2_2") (pintype "passive"))
      (node (ref "C47") (pin "2") (pinfunction "2_2") (pintype "passive"))
      (node (ref "C49") (pin "2") (pinfunction "2_2") (pintype "passive"))
      (node (ref "C5") (pin "-") (pinfunction "-_-") (pintype "passive"))
      (node (ref "C50") (pin "2") (pinfunction "2_2") (pintype "passive"))
      (node (ref "C51") (pin "2") (pinfunction "2_2") (pintype "passive"))
      (node (ref "C6") (pin "2") (pinfunction "2_2") (pintype "passive"))
      (node (ref "C7") (pin "2") (pinfunction "2_2") (pintype "passive"))
      (node (ref "C8") (pin "2") (pinfunction "2_2") (pintype "passive"))
      (node (ref "GND") (pin "TP") (pinfunction "TP_TP") (pintype "input"))
      (node (ref "I2C") (pin "3") (pinfunction "3_3") (pintype "passive"))
      (node (ref "IC1") (pin "14") (pinfunction "VNEG_3_14") (pintype "bidirectional"))
      (node (ref "IC1") (pin "19") (pinfunction "LGND_19") (pintype "power_in"))
      (node (ref "IC1") (pin "28") (pinfunction "VNEG_4_28") (pintype "bidirectional"))
      (node (ref "IC1") (pin "29") (pinfunction "EP_29") (pintype "power_in"))
      (node (ref "IC1") (pin "6") (pinfunction "VNEG_1_6") (pintype "bidirectional"))
      (node (ref "IC1") (pin "9") (pinfunction "VNEG_2_9") (pintype "bidirectional"))
      (node (ref "IC2") (pin "14") (pinfunction "VNEG_3_14") (pintype "bidirectional"))
      (node (ref "IC2") (pin "19") (pinfunction "LGND_19") (pintype "power_in"))
      (node (ref "IC2") (pin "28") (pinfunction "VNEG_4_28") (pintype "bidirectional"))
      (node (ref "IC2") (pin "29") (pinfunction "EP_29") (pintype "power_in"))
      (node (ref "IC2") (pin "6") (pinfunction "VNEG_1_6") (pintype "bidirectional"))
      (node (ref "IC2") (pin "9") (pinfunction "VNEG_2_9") (pintype "bidirectional"))
      (node (ref "INA219") (pin "3") (pinfunction "GND_3") (pintype "bidirectional"))
      (node (ref "INA219") (pin "7") (pinfunction "A0_7") (pintype "bidirectional"))
      (node (ref "INA219") (pin "8") (pinfunction "A1_8") (pintype "bidirectional"))
      (node (ref "J1") (pin "5") (pinfunction "5_5") (pintype "passive"))
      (node (ref "LDIAR") (pin "P4") (pinfunction "4_P4") (pintype "bidirectional"))
      (node (ref "LED1") (pin "1") (pinfunction "K_1") (pintype "bidirectional"))
      (node (ref "M1") (pin "2") (pinfunction "S_2") (pintype "passive"))
      (node (ref "M2") (pin "2") (pinfunction "S_2") (pintype "passive"))
      (node (ref "M3") (pin "2") (pinfunction "S_2") (pintype "passive"))
      (node (ref "P1") (pin "5") (pinfunction "5_5") (pintype "passive"))
      (node (ref "P2") (pin "5") (pinfunction "5_5") (pintype "passive"))
      (node (ref "P3") (pin "5") (pinfunction "5_5") (pintype "passive"))
      (node (ref "P4") (pin "5") (pinfunction "5_5") (pintype "passive"))
      (node (ref "PCA9533") (pin "4") (pinfunction "VSS_4") (pintype "power_in"))
      (node (ref "PWR") (pin "2") (pinfunction "2_2") (pintype "passive"))
      (node (ref "R11") (pin "1") (pinfunction "1_1") (pintype "passive"))
      (node (ref "R13") (pin "1") (pinfunction "1_1") (pintype "passive"))
      (node (ref "R35") (pin "1") (pinfunction "1_1") (pintype "passive"))
      (node (ref "R7") (pin "2") (pinfunction "2_2") (pintype "passive"))
      (node (ref "R9") (pin "1") (pinfunction "1_1") (pintype "passive"))
      (node (ref "RPI_ZERO") (pin "1") (pinfunction "1_1") (pintype "passive"))
      (node (ref "RPI_ZERO") (pin "12") (pinfunction "12_12") (pintype "passive"))
      (node (ref "RPI_ZERO") (pin "15") (pinfunction "15_15") (pintype "passive"))
      (node (ref "RPI_ZERO") (pin "22") (pinfunction "22_22") (pintype "passive"))
      (node (ref "RPI_ZERO") (pin "28") (pinfunction "28_28") (pintype "passive"))
      (node (ref "RPI_ZERO") (pin "31") (pinfunction "31_31") (pintype "passive"))
      (node (ref "RPI_ZERO") (pin "36") (pinfunction "36_36") (pintype "passive"))
      (node (ref "RPI_ZERO") (pin "8") (pinfunction "8_8") (pintype "passive"))
      (node (ref "SJ2") (pin "1") (pinfunction "1_1") (pintype "passive"))
      (node (ref "U1") (pin "10") (pinfunction "VSS_10") (pintype "power_in"))
      (node (ref "U1") (pin "20") (pinfunction "VSSA_20") (pintype "power_in"))
      (node (ref "U1") (pin "27") (pinfunction "VSS_27") (pintype "power_in"))
      (node (ref "U1") (pin "74") (pinfunction "VSS_74") (pintype "power_in"))
      (node (ref "U1") (pin "99") (pinfunction "VSS_99") (pintype "power_in"))
      (node (ref "U3") (pin "18") (pinfunction "GND_18") (pintype "power_in"))
      (node (ref "U5") (pin "4") (pinfunction "GND_4") (pintype "power_in"))
    )
    (net (code "56") (name "Net-(ABM8G-25.000MHZ-18-D2Y-T3-2)") (class "Default")
      (node (ref "ABM8G-25.000MHZ-18-D2Y-T3") (pin "3") (pinfunction "2_3") (pintype "passive"))
      (node (ref "C12") (pin "2") (pinfunction "2_2") (pintype "passive"))
      (node (ref "U1") (pin "12") (pinfunction "PH0_12") (pintype "bidirectional"))
    )
    (net (code "57") (name "Net-(D2-A)") (class "Default")
      (node (ref "D2") (pin "2") (pinfunction "A_2") (pintype "bidirectional"))
      (node (ref "J1") (pin "1") (pinfunction "1_1") (pintype "passive"))
    )
    (net (code "58") (name "Net-(FAN-2)") (class "Default")
      (node (ref "D3") (pin "A") (pinfunction "A_A") (pintype "passive"))
      (node (ref "FAN") (pin "P2") (pinfunction "2_P2") (pintype "bidirectional"))
      (node (ref "M2") (pin "3") (pinfunction "D_3") (pintype "passive"))
    )
    (net (code "59") (name "Net-(FRONTLIGHT-1)") (class "Default")
      (node (ref "FRONTLIGHT") (pin "P1") (pinfunction "1_P1") (pintype "bidirectional"))
      (node (ref "R3") (pin "2") (pinfunction "2_2") (pintype "passive"))
    )
    (net (code "60") (name "Net-(FRONTLIGHT-2)") (class "Default")
      (node (ref "FRONTLIGHT") (pin "P2") (pinfunction "2_P2") (pintype "bidirectional"))
      (node (ref "M3") (pin "3") (pinfunction "D_3") (pintype "passive"))
    )
    (net (code "61") (name "Net-(IC1-CP1)") (class "Default")
      (node (ref "C2") (pin "1") (pinfunction "1_1") (pintype "passive"))
      (node (ref "IC1") (pin "1") (pinfunction "CP1_1") (pintype "bidirectional"))
    )
    (net (code "62") (name "Net-(IC1-CP2)") (class "Default")
      (node (ref "C2") (pin "2") (pinfunction "2_2") (pintype "passive"))
      (node (ref "IC1") (pin "2") (pinfunction "CP2_2") (pintype "bidirectional"))
    )
    (net (code "63") (name "Net-(IC1-OUT1)") (class "Default")
      (node (ref "IC1") (pin "5") (pinfunction "OUT1_5") (pintype "output"))
      (node (ref "P3") (pin "1") (pinfunction "1_1") (pintype "passive"))
    )
    (net (code "64") (name "Net-(IC1-OUT2)") (class "Default")
      (node (ref "IC1") (pin "7") (pinfunction "OUT2_7") (pintype "output"))
      (node (ref "P3") (pin "6") (pinfunction "6_6") (pintype "passive"))
    )
    (net (code "65") (name "Net-(IC1-OUT3)") (class "Default")
      (node (ref "IC1") (pin "8") (pinfunction "OUT3_8") (pintype "output"))
      (node (ref "P1") (pin "6") (pinfunction "6_6") (pintype "passive"))
    )
    (net (code "66") (name "Net-(IC1-OUT4)") (class "Default")
      (node (ref "IC1") (pin "10") (pinfunction "OUT4_10") (pintype "output"))
      (node (ref "P1") (pin "1") (pinfunction "1_1") (pintype "passive"))
    )
    (net (code "67") (name "Net-(IC1-V3P3OUT)") (class "Default")
      (node (ref "C4") (pin "1") (pinfunction "1_1") (pintype "passive"))
      (node (ref "IC1") (pin "15") (pinfunction "V3P3OUT_15") (pintype "output"))
    )
    (net (code "68") (name "Net-(IC1-VCP)") (class "Default")
      (node (ref "C3") (pin "1") (pinfunction "1_1") (pintype "passive"))
      (node (ref "IC1") (pin "3") (pinfunction "VCP_3") (pintype "bidirectional"))
    )
    (net (code "69") (name "Net-(IC2-CP1)") (class "Default")
      (node (ref "C21") (pin "1") (pinfunction "1_1") (pintype "passive"))
      (node (ref "IC2") (pin "1") (pinfunction "CP1_1") (pintype "bidirectional"))
    )
    (net (code "70") (name "Net-(IC2-CP2)") (class "Default")
      (node (ref "C21") (pin "2") (pinfunction "2_2") (pintype "passive"))
      (node (ref "IC2") (pin "2") (pinfunction "CP2_2") (pintype "bidirectional"))
    )
    (net (code "71") (name "Net-(IC2-OUT1)") (class "Default")
      (node (ref "IC2") (pin "5") (pinfunction "OUT1_5") (pintype "output"))
      (node (ref "P4") (pin "1") (pinfunction "1_1") (pintype "passive"))
    )
    (net (code "72") (name "Net-(IC2-OUT2)") (class "Default")
      (node (ref "IC2") (pin "7") (pinfunction "OUT2_7") (pintype "output"))
      (node (ref "P4") (pin "6") (pinfunction "6_6") (pintype "passive"))
    )
    (net (code "73") (name "Net-(IC2-OUT3)") (class "Default")
      (node (ref "IC2") (pin "8") (pinfunction "OUT3_8") (pintype "output"))
      (node (ref "P2") (pin "6") (pinfunction "6_6") (pintype "passive"))
    )
    (net (code "74") (name "Net-(IC2-OUT4)") (class "Default")
      (node (ref "IC2") (pin "10") (pinfunction "OUT4_10") (pintype "output"))
      (node (ref "P2") (pin "1") (pinfunction "1_1") (pintype "passive"))
    )
    (net (code "75") (name "Net-(IC2-V3P3OUT)") (class "Default")
      (node (ref "C25") (pin "1") (pinfunction "1_1") (pintype "passive"))
      (node (ref "IC2") (pin "15") (pinfunction "V3P3OUT_15") (pintype "output"))
    )
    (net (code "76") (name "Net-(IC2-VCP)") (class "Default")
      (node (ref "C22") (pin "1") (pinfunction "1_1") (pintype "passive"))
      (node (ref "IC2") (pin "3") (pinfunction "VCP_3") (pintype "bidirectional"))
    )
    (net (code "77") (name "Net-(J1-Pad2)") (class "Default")
      (node (ref "J1") (pin "2") (pinfunction "2_2") (pintype "passive"))
      (node (ref "R14") (pin "2") (pinfunction "2_2") (pintype "passive"))
    )
    (net (code "78") (name "Net-(J1-Pad3)") (class "Default")
      (node (ref "J1") (pin "3") (pinfunction "3_3") (pintype "passive"))
      (node (ref "R12") (pin "1") (pinfunction "1_1") (pintype "passive"))
      (node (ref "R18") (pin "2") (pinfunction "2_2") (pintype "passive"))
    )
    (net (code "79") (name "Net-(J1-Pad4)") (class "Default")
      (node (ref "J1") (pin "4") (pinfunction "4_4") (pintype "passive"))
      (node (ref "R16") (pin "2") (pinfunction "2_2") (pintype "passive"))
    )
    (net (code "80") (name "Net-(J1-SHIELD-PadSH1)") (class "Default")
      (node (ref "J1") (pin "SH1") (pinfunction "SHIELD_SH1") (pintype "passive"))
      (node (ref "J1") (pin "SH2") (pinfunction "SHIELD_SH2") (pintype "passive"))
      (node (ref "J1") (pin "SH3") (pinfunction "SHIELD_SH3") (pintype "passive"))
      (node (ref "J1") (pin "SH4") (pinfunction "SHIELD_SH4") (pintype "passive"))
      (node (ref "J1") (pin "SH5") (pinfunction "SHIELD_SH5") (pintype "passive"))
      (node (ref "R19") (pin "2") (pinfunction "2_2") (pintype "passive"))
    )
    (net (code "81") (name "Net-(LED1-A)") (class "Default")
      (node (ref "LED1") (pin "2") (pinfunction "A_2") (pintype "bidirectional"))
      (node (ref "R5") (pin "1") (pinfunction "1_1") (pintype "passive"))
    )
    (net (code "82") (name "Net-(LIDAR_MOTOR-1)") (class "Default")
      (node (ref "D1") (pin "A") (pinfunction "A_A") (pintype "passive"))
      (node (ref "LIDAR_MOTOR") (pin "P1") (pinfunction "1_P1") (pintype "bidirectional"))
      (node (ref "M1") (pin "3") (pinfunction "D_3") (pintype "passive"))
    )
    (net (code "83") (name "Net-(M1-G)") (class "Default")
      (node (ref "M1") (pin "1") (pinfunction "G_1") (pintype "passive"))
      (node (ref "R38") (pin "2") (pinfunction "2_2") (pintype "passive"))
      (node (ref "R9") (pin "2") (pinfunction "2_2") (pintype "passive"))
    )
    (net (code "84") (name "Net-(M2-G)") (class "Default")
      (node (ref "M2") (pin "1") (pinfunction "G_1") (pintype "passive"))
      (node (ref "R13") (pin "2") (pinfunction "2_2") (pintype "passive"))
      (node (ref "R22") (pin "2") (pinfunction "2_2") (pintype "passive"))
    )
    (net (code "85") (name "Net-(M3-G)") (class "Default")
      (node (ref "M3") (pin "1") (pinfunction "G_1") (pintype "passive"))
      (node (ref "R11") (pin "2") (pinfunction "2_2") (pintype "passive"))
      (node (ref "R6") (pin "2") (pinfunction "2_2") (pintype "passive"))
    )
    (net (code "86") (name "Net-(P1-Pad2)") (class "Default")
      (node (ref "P1") (pin "2") (pinfunction "2_2") (pintype "passive"))
      (node (ref "P2") (pin "2") (pinfunction "2_2") (pintype "passive"))
      (node (ref "P3") (pin "2") (pinfunction "2_2") (pintype "passive"))
      (node (ref "P4") (pin "2") (pinfunction "2_2") (pintype "passive"))
      (node (ref "SJ1") (pin "2") (pinfunction "2_2") (pintype "passive"))
    )
    (net (code "87") (name "Net-(PCA9533-LED0)") (class "Default")
      (node (ref "PCA9533") (pin "1") (pinfunction "LED0_1") (pintype "bidirectional"))
      (node (ref "R28") (pin "1") (pinfunction "1_1") (pintype "passive"))
    )
    (net (code "88") (name "Net-(PCA9533-LED1)") (class "Default")
      (node (ref "PCA9533") (pin "2") (pinfunction "LED1_2") (pintype "bidirectional"))
      (node (ref "R27") (pin "1") (pinfunction "1_1") (pintype "passive"))
    )
    (net (code "89") (name "Net-(PCA9533-LED2)") (class "Default")
      (node (ref "PCA9533") (pin "3") (pinfunction "LED2_3") (pintype "bidirectional"))
      (node (ref "R26") (pin "1") (pinfunction "1_1") (pintype "passive"))
    )
    (net (code "90") (name "Net-(R19-Pad1)") (class "Default")
      (node (ref "R19") (pin "1") (pinfunction "1_1") (pintype "passive"))
      (node (ref "SJ2") (pin "2") (pinfunction "2_2") (pintype "passive"))
    )
    (net (code "91") (name "Net-(RGB_LED-2)") (class "Default")
      (node (ref "R28") (pin "2") (pinfunction "2_2") (pintype "passive"))
      (node (ref "RGB_LED") (pin "P2") (pinfunction "2_P2") (pintype "bidirectional"))
    )
    (net (code "92") (name "Net-(RGB_LED-3)") (class "Default")
      (node (ref "R27") (pin "2") (pinfunction "2_2") (pintype "passive"))
      (node (ref "RGB_LED") (pin "P3") (pinfunction "3_P3") (pintype "bidirectional"))
    )
    (net (code "93") (name "Net-(RGB_LED-4)") (class "Default")
      (node (ref "R26") (pin "2") (pinfunction "2_2") (pintype "passive"))
      (node (ref "RGB_LED") (pin "P4") (pinfunction "4_P4") (pintype "bidirectional"))
    )
    (net (code "94") (name "Net-(U1-BOOT0)") (class "Default")
      (node (ref "R7") (pin "1") (pinfunction "1_1") (pintype "passive"))
      (node (ref "U1") (pin "94") (pinfunction "BOOT0_94") (pintype "input"))
    )
    (net (code "95") (name "Net-(U1-PH1)") (class "Default")
      (node (ref "ABM8G-25.000MHZ-18-D2Y-T3") (pin "1") (pinfunction "1_1") (pintype "passive"))
      (node (ref "C11") (pin "2") (pinfunction "2_2") (pintype "passive"))
      (node (ref "U1") (pin "13") (pinfunction "PH1_13") (pintype "bidirectional"))
    )
    (net (code "96") (name "Net-(U1-VCAP_1)") (class "Default")
      (node (ref "C29") (pin "2") (pinfunction "2_2") (pintype "passive"))
      (node (ref "U1") (pin "49") (pinfunction "VCAP_1_49") (pintype "power_in"))
    )
    (net (code "97") (name "Net-(U1-VCAP_2)") (class "Default")
      (node (ref "C32") (pin "2") (pinfunction "2_2") (pintype "passive"))
      (node (ref "U1") (pin "73") (pinfunction "VCAP_2_73") (pintype "power_in"))
    )
    (net (code "98") (name "Net-(U3-REGOUT)") (class "Default")
      (node (ref "C7") (pin "1") (pinfunction "1_1") (pintype "passive"))
      (node (ref "U3") (pin "10") (pinfunction "REGOUT_10") (pintype "output"))
    )
    (net (code "99") (name "V+") (class "Default")
      (node (ref "C16") (pin "1") (pinfunction "1_1") (pintype "passive"))
      (node (ref "C27") (pin "+") (pinfunction "+_+") (pintype "passive"))
      (node (ref "INA219") (pin "1") (pinfunction "VIN+_1") (pintype "bidirectional"))
      (node (ref "PWR") (pin "1") (pinfunction "1_1") (pintype "passive"))
      (node (ref "R17") (pin "2") (pinfunction "2_2") (pintype "passive"))
      (node (ref "R34") (pin "2") (pinfunction "2_2") (pintype "passive"))
    )
    (net (code "100") (name "unconnected-(IC1-NC_1-Pad12)") (class "Default")
      (node (ref "IC1") (pin "12") (pinfunction "NC_1_12") (pintype "bidirectional"))
    )
    (net (code "101") (name "unconnected-(IC1-NC_2-Pad13)") (class "Default")
      (node (ref "IC1") (pin "13") (pinfunction "NC_2_13") (pintype "bidirectional"))
    )
    (net (code "102") (name "unconnected-(IC2-NC_1-Pad12)") (class "Default")
      (node (ref "IC2") (pin "12") (pinfunction "NC_1_12") (pintype "bidirectional"))
    )
    (net (code "103") (name "unconnected-(IC2-NC_2-Pad13)") (class "Default")
      (node (ref "IC2") (pin "13") (pinfunction "NC_2_13") (pintype "bidirectional"))
    )
    (net (code "104") (name "unconnected-(PCA9533-LED3-Pad5)") (class "Default")
      (node (ref "PCA9533") (pin "5") (pinfunction "LED3_5") (pintype "bidirectional"))
    )
    (net (code "105") (name "unconnected-(RPI_ZERO-Pad2)") (class "Default")
      (node (ref "RPI_ZERO") (pin "2") (pinfunction "2_2") (pintype "passive"))
    )
    (net (code "106") (name "unconnected-(RPI_ZERO-Pad3)") (class "Default")
      (node (ref "RPI_ZERO") (pin "3") (pinfunction "3_3") (pintype "passive"))
    )
    (net (code "107") (name "unconnected-(RPI_ZERO-Pad4)") (class "Default")
      (node (ref "RPI_ZERO") (pin "4") (pinfunction "4_4") (pintype "passive"))
    )
    (net (code "108") (name "unconnected-(RPI_ZERO-Pad5)") (class "Default")
      (node (ref "RPI_ZERO") (pin "5") (pinfunction "5_5") (pintype "passive"))
    )
    (net (code "109") (name "unconnected-(RPI_ZERO-Pad6)") (class "Default")
      (node (ref "RPI_ZERO") (pin "6") (pinfunction "6_6") (pintype "passive"))
    )
    (net (code "110") (name "unconnected-(RPI_ZERO-Pad7)") (class "Default")
      (node (ref "RPI_ZERO") (pin "7") (pinfunction "7_7") (pintype "passive"))
    )
    (net (code "111") (name "unconnected-(RPI_ZERO-Pad9)") (class "Default")
      (node (ref "RPI_ZERO") (pin "9") (pinfunction "9_9") (pintype "passive"))
    )
    (net (code "112") (name "unconnected-(RPI_ZERO-Pad10)") (class "Default")
      (node (ref "RPI_ZERO") (pin "10") (pinfunction "10_10") (pintype "passive"))
    )
    (net (code "113") (name "unconnected-(RPI_ZERO-Pad11)") (class "Default")
      (node (ref "RPI_ZERO") (pin "11") (pinfunction "11_11") (pintype "passive"))
    )
    (net (code "114") (name "unconnected-(RPI_ZERO-Pad13)") (class "Default")
      (node (ref "RPI_ZERO") (pin "13") (pinfunction "13_13") (pintype "passive"))
    )
    (net (code "115") (name "unconnected-(RPI_ZERO-Pad14)") (class "Default")
      (node (ref "RPI_ZERO") (pin "14") (pinfunction "14_14") (pintype "passive"))
    )
    (net (code "116") (name "unconnected-(RPI_ZERO-Pad16)") (class "Default")
      (node (ref "RPI_ZERO") (pin "16") (pinfunction "16_16") (pintype "passive"))
    )
    (net (code "117") (name "unconnected-(RPI_ZERO-Pad17)") (class "Default")
      (node (ref "RPI_ZERO") (pin "17") (pinfunction "17_17") (pintype "passive"))
    )
    (net (code "118") (name "unconnected-(RPI_ZERO-Pad18)") (class "Default")
      (node (ref "RPI_ZERO") (pin "18") (pinfunction "18_18") (pintype "passive"))
    )
    (net (code "119") (name "unconnected-(RPI_ZERO-Pad19)") (class "Default")
      (node (ref "RPI_ZERO") (pin "19") (pinfunction "19_19") (pintype "passive"))
    )
    (net (code "120") (name "unconnected-(RPI_ZERO-Pad21)") (class "Default")
      (node (ref "RPI_ZERO") (pin "21") (pinfunction "21_21") (pintype "passive"))
    )
    (net (code "121") (name "unconnected-(RPI_ZERO-Pad23)") (class "Default")
      (node (ref "RPI_ZERO") (pin "23") (pinfunction "23_23") (pintype "passive"))
    )
    (net (code "122") (name "unconnected-(RPI_ZERO-Pad25)") (class "Default")
      (node (ref "RPI_ZERO") (pin "25") (pinfunction "25_25") (pintype "passive"))
    )
    (net (code "123") (name "unconnected-(RPI_ZERO-Pad27)") (class "Default")
      (node (ref "RPI_ZERO") (pin "27") (pinfunction "27_27") (pintype "passive"))
    )
    (net (code "124") (name "unconnected-(RPI_ZERO-Pad29)") (class "Default")
      (node (ref "RPI_ZERO") (pin "29") (pinfunction "29_29") (pintype "passive"))
    )
    (net (code "125") (name "unconnected-(RPI_ZERO-Pad30)") (class "Default")
      (node (ref "RPI_ZERO") (pin "30") (pinfunction "30_30") (pintype "passive"))
    )
    (net (code "126") (name "unconnected-(RPI_ZERO-Pad33)") (class "Default")
      (node (ref "RPI_ZERO") (pin "33") (pinfunction "33_33") (pintype "passive"))
    )
    (net (code "127") (name "unconnected-(RPI_ZERO-Pad35)") (class "Default")
      (node (ref "RPI_ZERO") (pin "35") (pinfunction "35_35") (pintype "passive"))
    )
    (net (code "128") (name "unconnected-(RPI_ZERO-Pad37)") (class "Default")
      (node (ref "RPI_ZERO") (pin "37") (pinfunction "37_37") (pintype "passive"))
    )
    (net (code "129") (name "unconnected-(RPI_ZERO-Pad39)") (class "Default")
      (node (ref "RPI_ZERO") (pin "39") (pinfunction "39_39") (pintype "passive"))
    )
    (net (code "130") (name "unconnected-(U1-PA4-Pad29)") (class "Default")
      (node (ref "U1") (pin "29") (pinfunction "PA4_29") (pintype "bidirectional"))
    )
    (net (code "131") (name "unconnected-(U1-PA5-Pad30)") (class "Default")
      (node (ref "U1") (pin "30") (pinfunction "PA5_30") (pintype "bidirectional"))
    )
    (net (code "132") (name "unconnected-(U1-PA15-Pad77)") (class "Default")
      (node (ref "U1") (pin "77") (pinfunction "PA15_77") (pintype "bidirectional"))
    )
    (net (code "133") (name "unconnected-(U1-PB2-Pad37)") (class "Default")
      (node (ref "U1") (pin "37") (pinfunction "PB2_37") (pintype "bidirectional"))
    )
    (net (code "134") (name "unconnected-(U1-PB5-Pad91)") (class "Default")
      (node (ref "U1") (pin "91") (pinfunction "PB5_91") (pintype "bidirectional"))
    )
    (net (code "135") (name "unconnected-(U1-PB12-Pad51)") (class "Default")
      (node (ref "U1") (pin "51") (pinfunction "PB12_51") (pintype "bidirectional"))
    )
    (net (code "136") (name "unconnected-(U1-PB13-Pad52)") (class "Default")
      (node (ref "U1") (pin "52") (pinfunction "PB13_52") (pintype "bidirectional"))
    )
    (net (code "137") (name "unconnected-(U1-PB14-Pad53)") (class "Default")
      (node (ref "U1") (pin "53") (pinfunction "PB14_53") (pintype "bidirectional"))
    )
    (net (code "138") (name "unconnected-(U1-PB15-Pad54)") (class "Default")
      (node (ref "U1") (pin "54") (pinfunction "PB15_54") (pintype "bidirectional"))
    )
    (net (code "139") (name "unconnected-(U1-PC1-Pad16)") (class "Default")
      (node (ref "U1") (pin "16") (pinfunction "PC1_16") (pintype "bidirectional"))
    )
    (net (code "140") (name "unconnected-(U1-PC2-Pad17)") (class "Default")
      (node (ref "U1") (pin "17") (pinfunction "PC2_17") (pintype "bidirectional"))
    )
    (net (code "141") (name "unconnected-(U1-PC3-Pad18)") (class "Default")
      (node (ref "U1") (pin "18") (pinfunction "PC3_18") (pintype "bidirectional"))
    )
    (net (code "142") (name "unconnected-(U1-PC4-Pad33)") (class "Default")
      (node (ref "U1") (pin "33") (pinfunction "PC4_33") (pintype "bidirectional"))
    )
    (net (code "143") (name "unconnected-(U1-PC5-Pad34)") (class "Default")
      (node (ref "U1") (pin "34") (pinfunction "PC5_34") (pintype "bidirectional"))
    )
    (net (code "144") (name "unconnected-(U1-PC8-Pad65)") (class "Default")
      (node (ref "U1") (pin "65") (pinfunction "PC8_65") (pintype "bidirectional"))
    )
    (net (code "145") (name "unconnected-(U1-PC13-Pad7)") (class "Default")
      (node (ref "U1") (pin "7") (pinfunction "PC13_7") (pintype "bidirectional"))
    )
    (net (code "146") (name "unconnected-(U1-PC14-Pad8)") (class "Default")
      (node (ref "U1") (pin "8") (pinfunction "PC14_8") (pintype "bidirectional"))
    )
    (net (code "147") (name "unconnected-(U1-PC15-Pad9)") (class "Default")
      (node (ref "U1") (pin "9") (pinfunction "PC15_9") (pintype "bidirectional"))
    )
    (net (code "148") (name "unconnected-(U1-PD10-Pad57)") (class "Default")
      (node (ref "U1") (pin "57") (pinfunction "PD10_57") (pintype "bidirectional"))
    )
    (net (code "149") (name "unconnected-(U1-PD11-Pad58)") (class "Default")
      (node (ref "U1") (pin "58") (pinfunction "PD11_58") (pintype "bidirectional"))
    )
    (net (code "150") (name "unconnected-(U1-PD14-Pad61)") (class "Default")
      (node (ref "U1") (pin "61") (pinfunction "PD14_61") (pintype "bidirectional"))
    )
    (net (code "151") (name "unconnected-(U1-PD15-Pad62)") (class "Default")
      (node (ref "U1") (pin "62") (pinfunction "PD15_62") (pintype "bidirectional"))
    )
    (net (code "152") (name "unconnected-(U1-PE0-Pad97)") (class "Default")
      (node (ref "U1") (pin "97") (pinfunction "PE0_97") (pintype "bidirectional"))
    )
    (net (code "153") (name "unconnected-(U1-PE1-Pad98)") (class "Default")
      (node (ref "U1") (pin "98") (pinfunction "PE1_98") (pintype "bidirectional"))
    )
    (net (code "154") (name "unconnected-(U1-PE2-Pad1)") (class "Default")
      (node (ref "U1") (pin "1") (pinfunction "PE2_1") (pintype "bidirectional"))
    )
    (net (code "155") (name "unconnected-(U1-PE3-Pad2)") (class "Default")
      (node (ref "U1") (pin "2") (pinfunction "PE3_2") (pintype "bidirectional"))
    )
    (net (code "156") (name "unconnected-(U1-PE4-Pad3)") (class "Default")
      (node (ref "U1") (pin "3") (pinfunction "PE4_3") (pintype "bidirectional"))
    )
    (net (code "157") (name "unconnected-(U1-PE7-Pad38)") (class "Default")
      (node (ref "U1") (pin "38") (pinfunction "PE7_38") (pintype "bidirectional"))
    )
    (net (code "158") (name "unconnected-(U1-PE8-Pad39)") (class "Default")
      (node (ref "U1") (pin "39") (pinfunction "PE8_39") (pintype "bidirectional"))
    )
    (net (code "159") (name "unconnected-(U1-PE10-Pad41)") (class "Default")
      (node (ref "U1") (pin "41") (pinfunction "PE10_41") (pintype "bidirectional"))
    )
    (net (code "160") (name "unconnected-(U1-PE12-Pad43)") (class "Default")
      (node (ref "U1") (pin "43") (pinfunction "PE12_43") (pintype "bidirectional"))
    )
    (net (code "161") (name "unconnected-(U1-PE15-Pad46)") (class "Default")
      (node (ref "U1") (pin "46") (pinfunction "PE15_46") (pintype "bidirectional"))
    )
    (net (code "162") (name "unconnected-(U3-AD0{slash}SDO-Pad9)") (class "Default")
      (node (ref "U3") (pin "9") (pinfunction "AD0/SDO_9") (pintype "output"))
    )
    (net (code "163") (name "unconnected-(U3-AUX_CL-Pad7)") (class "Default")
      (node (ref "U3") (pin "7") (pinfunction "AUX_CL_7") (pintype "input"))
    )
    (net (code "164") (name "unconnected-(U3-AUX_DA-Pad21)") (class "Default")
      (node (ref "U3") (pin "21") (pinfunction "AUX_DA_21") (pintype "input"))
    )
    (net (code "165") (name "unconnected-(U3-FSYNC-Pad11)") (class "Default")
      (node (ref "U3") (pin "11") (pinfunction "FSYNC_11") (pintype "input"))
    )
    (net (code "166") (name "unconnected-(U3-INT1-Pad12)") (class "Default")
      (node (ref "U3") (pin "12") (pinfunction "INT1_12") (pintype "output"))
    )
    (net (code "167") (name "unconnected-(U3-NCS-Pad22)") (class "Default")
      (node (ref "U3") (pin "22") (pinfunction "NCS_22") (pintype "input"))
    )
    (net (code "168") (name "unconnected-(U3-RESV_19-Pad19)") (class "Default")
      (node (ref "U3") (pin "19") (pinfunction "RESV_19_19") (pintype "passive"))
    )
    (net (code "169") (name "unconnected-(U3-RESV_20-Pad20)") (class "Default")
      (node (ref "U3") (pin "20") (pinfunction "RESV_20_20") (pintype "passive"))
    )
  )
)
